# STM3205P_DigitalOutputs.net
KiCad netlist of a schematic drawn in Altium Designer
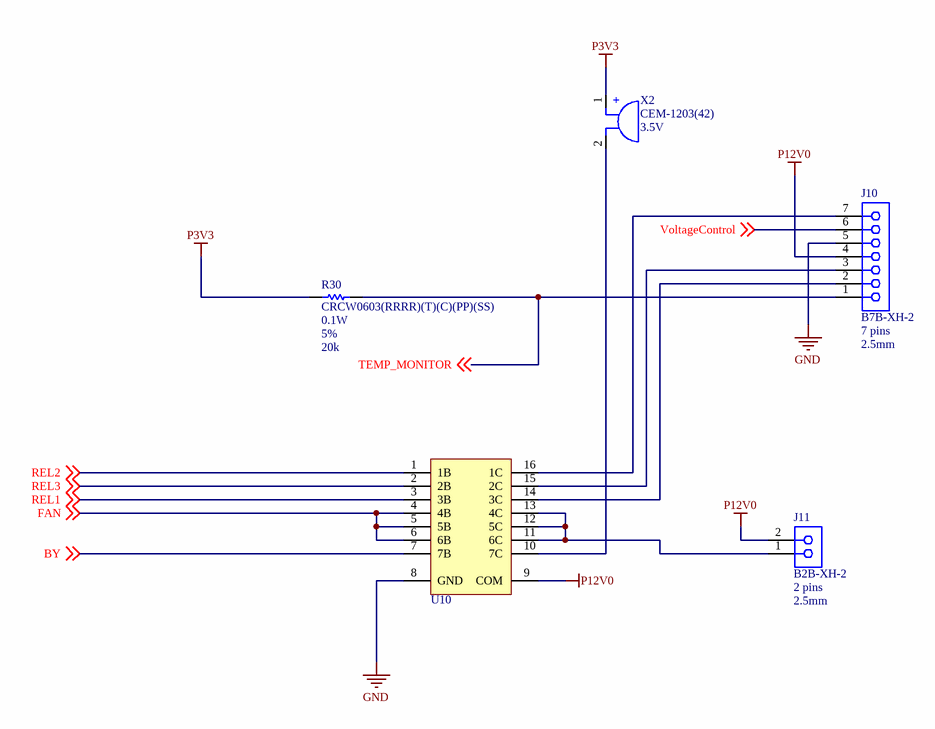
[diagram p0: STM3205P_DigitalOutputs.SchDoc]

(export (version "E")
  (design (tool "Eeschema 10.0.6"))
  (components
    (comp (ref "J10")
      (value "B7B-XH-2")
      (footprint "CONXH07STRMALE_2.5")
      (description "XH Connector 7 POS HDR VERT 2.5mm")
      (fields
        (field (name "PARTNUMBER1") "B7B-XH-2")
        (field (name "PINS") "7 pins")
        (field (name "PITCH") "2.5mm")
        (field (name "PUBLISHER") "Lucas Moraes")
      )
      (libsource (lib "XHConnector") (part "B7B-XH-2"))
    )
    (comp (ref "J11")
      (value "B2B-XH-2")
      (footprint "CONXH02STRMALE_2.5")
      (description "XH Connector 2 POS HDR VERT 2.5mm")
      (fields
        (field (name "PARTNUMBER1") "B2B-XH-2")
        (field (name "PINS") "2 pins")
        (field (name "PITCH") "2.5mm")
        (field (name "PUBLISHER") "Lucas Moraes")
      )
      (libsource (lib "XHConnector") (part "B2B-XH-2"))
    )
    (comp (ref "R30")
      (value "20k")
      (footprint "RES0603")
      (description "Thick Film Chip Resistors with CECC Approval,  available with Established Reliability")
      (fields
        (field (name "PARTNUMBER1") "CRCW0603(RRRR)(T)(C)(PP)(SS)")
        (field (name "POWER") "0.1W")
        (field (name "TOLERANCE") "5%")
        (field (name "Comment") "Chip Resistor")
        (field (name "PUBLISHER") "Lucas Moraes")
      )
      (libsource (lib "ResistorsFixed") (part "CRCW0603"))
    )
    (comp (ref "U10")
      (value "ULN2003ADR")
      (footprint "SOIC-16-3.9mm")
      (description "Darlington Transistors Arrays NPN 7-Ch")
      (fields (field (name "PUBLISHER") "Lucas Moraes"))
      (libsource (lib "Darlington Transistor Arrays") (part "ULN2003ADR"))
    )
    (comp (ref "X2")
      (value "3.5V")
      (footprint "CEM-1203")
      (description "12 mm, 3.5 Vo-p, 95 dB, Through Hole, Magnetic Audio Transducer Buzzer")
      (fields
        (field (name "PARTNUMBER1") "CEM-1203(42)")
        (field (name "Comment") "CEM-1203(42)")
        (field (name "PUBLISHER") "Lucas Moraes")
      )
      (libsource (lib "AudioIndicators") (part "CEM-1203(42)"))
    )
  )
  (nets
    (net (code "1") (name "BY") (class "Default")
      (node (ref "U10") (pin "7") (pinfunction "7B_7") (pintype "passive"))
    )
    (net (code "2") (name "FAN") (class "Default")
      (node (ref "U10") (pin "4") (pinfunction "4B_4") (pintype "passive"))
      (node (ref "U10") (pin "5") (pinfunction "5B_5") (pintype "passive"))
      (node (ref "U10") (pin "6") (pinfunction "6B_6") (pintype "passive"))
    )
    (net (code "3") (name "GND") (class "Default")
      (node (ref "J10") (pin "5") (pinfunction "5_5") (pintype "passive"))
      (node (ref "U10") (pin "8") (pinfunction "GND_8") (pintype "power_in"))
    )
    (net (code "4") (name "Net-(U10-1C)") (class "Default")
      (node (ref "J10") (pin "7") (pinfunction "7_7") (pintype "passive"))
      (node (ref "U10") (pin "16") (pinfunction "1C_16") (pintype "open_collector"))
    )
    (net (code "5") (name "Net-(U10-2C)") (class "Default")
      (node (ref "J10") (pin "3") (pinfunction "3_3") (pintype "passive"))
      (node (ref "U10") (pin "15") (pinfunction "2C_15") (pintype "open_collector"))
    )
    (net (code "6") (name "Net-(U10-3C)") (class "Default")
      (node (ref "J10") (pin "2") (pinfunction "2_2") (pintype "passive"))
      (node (ref "U10") (pin "14") (pinfunction "3C_14") (pintype "open_collector"))
    )
    (net (code "7") (name "Net-(U10-4C)") (class "Default")
      (node (ref "J11") (pin "1") (pinfunction "1_1") (pintype "passive"))
      (node (ref "U10") (pin "11") (pinfunction "6C_11") (pintype "open_collector"))
      (node (ref "U10") (pin "12") (pinfunction "5C_12") (pintype "open_collector"))
      (node (ref "U10") (pin "13") (pinfunction "4C_13") (pintype "open_collector"))
    )
    (net (code "8") (name "Net-(U10-7C)") (class "Default")
      (node (ref "U10") (pin "10") (pinfunction "7C_10") (pintype "open_collector"))
      (node (ref "X2") (pin "2") (pinfunction "-_2") (pintype "passive"))
    )
    (net (code "9") (name "P3V3") (class "Default")
      (node (ref "R30") (pin "2") (pinfunction "2_2") (pintype "passive"))
      (node (ref "X2") (pin "1") (pinfunction "+_1") (pintype "passive"))
    )
    (net (code "10") (name "P12V0") (class "Default")
      (node (ref "J10") (pin "4") (pinfunction "4_4") (pintype "passive"))
      (node (ref "J11") (pin "2") (pinfunction "2_2") (pintype "passive"))
      (node (ref "U10") (pin "9") (pinfunction "COM_9") (pintype "passive"))
    )
    (net (code "11") (name "REL1") (class "Default")
      (node (ref "U10") (pin "3") (pinfunction "3B_3") (pintype "passive"))
    )
    (net (code "12") (name "REL2") (class "Default")
      (node (ref "U10") (pin "1") (pinfunction "1B_1") (pintype "passive"))
    )
    (net (code "13") (name "REL3") (class "Default")
      (node (ref "U10") (pin "2") (pinfunction "2B_2") (pintype "passive"))
    )
    (net (code "14") (name "TEMP_MONITOR") (class "Default")
      (node (ref "J10") (pin "1") (pinfunction "1_1") (pintype "passive"))
      (node (ref "R30") (pin "1") (pinfunction "1_1") (pintype "passive"))
    )
    (net (code "15") (name "VoltageControl") (class "Default")
      (node (ref "J10") (pin "6") (pinfunction "6_6") (pintype "passive"))
    )
  )
)
